# 5_spi_memory.net
KiCad netlist of a schematic drawn in Altium Designer
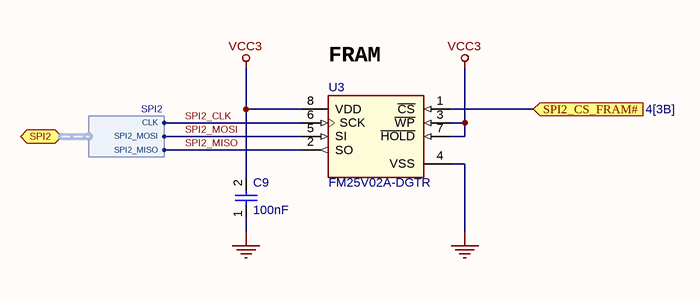
[diagram p0: 5_spi_memory.SchDoc]

(export (version "E")
  (design (tool "Eeschema 10.0.6"))
  (components
    (comp (ref "C9")
      (value "100nF")
      (footprint "CAPC0402(1005)60_L")
      (description "Chip Capacitor, 100nF +/-20%, 10V, 0402, Thickness 0.6 mm")
      (fields (field (name "TOLERANCE") "20%") (field (name "Comment") "Capacitor 100nF +/-20% 10V 0402"))
      (libsource (lib "<Company> Server") (part "CAP-NP-2"))
    )
    (comp (ref "U3")
      (value "FM25V02A-DGTR")
      (footprint "SON95P400X75_HS-9N")
      (description "REEL / F-RAM Memory Serial")
      (libsource (lib "<Company> Server") (part "CMP-019-00000-4"))
    )
  )
  (nets
    (net (code "2") (name "/SPI2_CLK") (class "Default")
      (node (ref "U3") (pin "6") (pinfunction "SCK_6") (pintype "input"))
    )
    (net (code "3") (name "/SPI2_CS_FRAM#") (class "Default")
      (node (ref "U3") (pin "1") (pinfunction "~{CS}_1") (pintype "input"))
    )
    (net (code "4") (name "/SPI2_MISO") (class "Default")
      (node (ref "U3") (pin "2") (pinfunction "SO_2") (pintype "output"))
    )
    (net (code "5") (name "/SPI2_MOSI") (class "Default")
      (node (ref "U3") (pin "5") (pinfunction "SI_5") (pintype "input"))
    )
    (net (code "7") (name "GND") (class "Default")
      (node (ref "C9") (pin "1") (pinfunction "1_1") (pintype "passive"))
      (node (ref "U3") (pin "4") (pinfunction "VSS_4") (pintype "power_in"))
    )
    (net (code "8") (name "VCC3") (class "Default")
      (node (ref "C9") (pin "2") (pinfunction "2_2") (pintype "passive"))
      (node (ref "U3") (pin "3") (pinfunction "~{WP}_3") (pintype "input"))
      (node (ref "U3") (pin "7") (pinfunction "~{HOLD}_7") (pintype "input"))
      (node (ref "U3") (pin "8") (pinfunction "VDD_8") (pintype "power_in"))
    )
  )
)
